# MesureAlimentation.net
KiCad netlist of a schematic drawn in Altium Designer
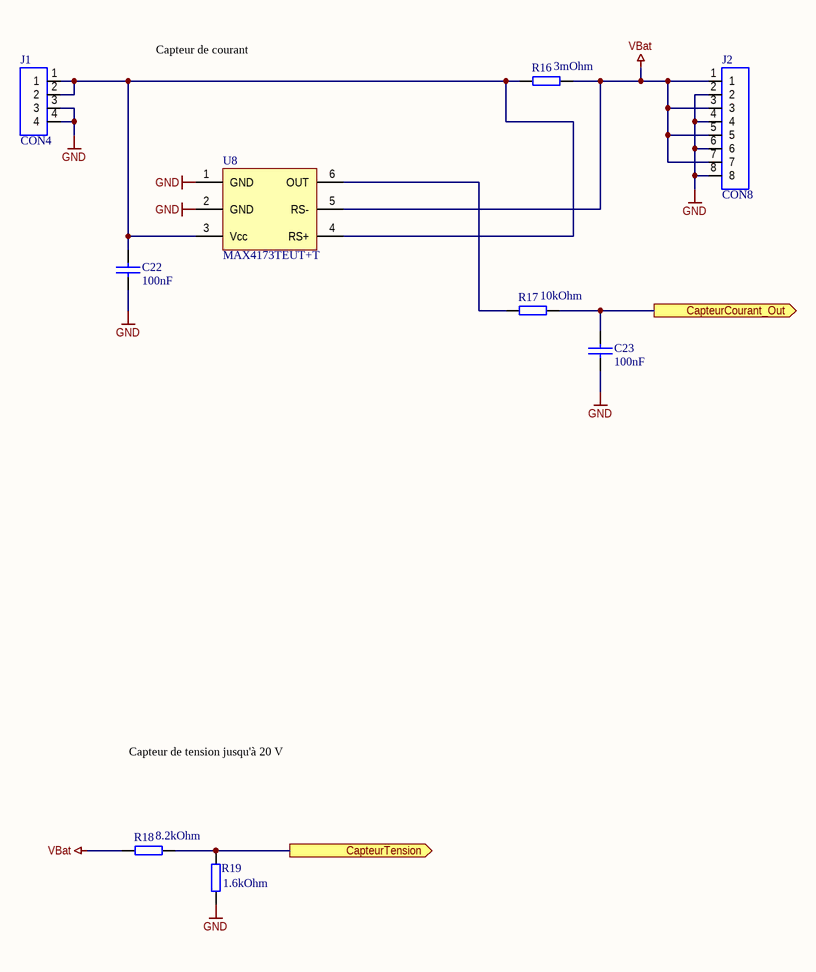
[diagram p0: MesureAlimentation.SchDoc]

(export (version "E")
  (design (tool "Eeschema 10.0.6"))
  (components
    (comp (ref "C22")
      (value "100nF")
      (footprint "060301")
      (description "CAPA")
      (fields (field (name "Comment") "GRM188R71E104KA01D"))
      (libsource (lib "General-Sch-205") (part "CAPA"))
    )
    (comp (ref "C23")
      (value "100nF")
      (footprint "060301")
      (description "CAPA")
      (fields (field (name "Comment") "GRM188R71E104KA01D"))
      (libsource (lib "General-Sch-205") (part "CAPA"))
    )
    (comp (ref "J1") (value "CON4") (footprint "SL354D") (libsource (lib "EISI") (part "CON4")))
    (comp (ref "J2") (value "CON8") (footprint "SL358D") (libsource (lib "EISI") (part "CON8")))
    (comp (ref "R16")
      (value "3mOhm")
      (footprint "5.2x8.75")
      (fields (field (name "Comment") "WSLP59313L000FEB"))
      (libsource (lib "General-Sch-205") (part "RES"))
    )
    (comp (ref "R17")
      (value "10kOhm")
      (footprint "080501")
      (fields (field (name "Comment") "ERJ-6GEYJ103V"))
      (libsource (lib "General-Sch-205") (part "RES"))
    )
    (comp (ref "R18")
      (value "8.2kOhm")
      (footprint "080501")
      (fields (field (name "Comment") "ERJ-6GEYJ822V"))
      (libsource (lib "General-Sch-205") (part "RES"))
    )
    (comp (ref "R19")
      (value "1.6kOhm")
      (footprint "080501")
      (fields (field (name "Comment") "ERJ-6GEYJ162V"))
      (libsource (lib "General-Sch-205") (part "RES"))
    )
    (comp (ref "U8")
      (value "MAX4173TEUT+T")
      (footprint "SOT26A-6AM")
      (description "Amplificateur capteur de courant")
      (libsource (lib "Schlib1") (part "Max4173"))
    )
  )
  (nets
    (net (code "1") (name "/CapteurCourant_Out") (class "Default")
      (node (ref "C23") (pin "1") (pintype "passive"))
      (node (ref "R17") (pin "2") (pintype "passive"))
    )
    (net (code "2") (name "/CapteurTension") (class "Default")
      (node (ref "R18") (pin "2") (pintype "passive"))
      (node (ref "R19") (pin "1") (pintype "passive"))
    )
    (net (code "3") (name "GND") (class "Default")
      (node (ref "C22") (pin "2") (pintype "passive"))
      (node (ref "C23") (pin "2") (pintype "passive"))
      (node (ref "J1") (pin "3") (pinfunction "3_3") (pintype "passive"))
      (node (ref "J1") (pin "4") (pinfunction "4_4") (pintype "passive"))
      (node (ref "J2") (pin "2") (pinfunction "2_2") (pintype "passive"))
      (node (ref "J2") (pin "4") (pinfunction "4_4") (pintype "passive"))
      (node (ref "J2") (pin "6") (pinfunction "6_6") (pintype "passive"))
      (node (ref "J2") (pin "8") (pinfunction "8_8") (pintype "passive"))
      (node (ref "R19") (pin "2") (pintype "passive"))
      (node (ref "U8") (pin "1") (pinfunction "GND_1") (pintype "passive"))
      (node (ref "U8") (pin "2") (pinfunction "GND_2") (pintype "passive"))
    )
    (net (code "4") (name "Net-(U8-OUT)") (class "Default")
      (node (ref "R17") (pin "1") (pintype "passive"))
      (node (ref "U8") (pin "6") (pinfunction "OUT_6") (pintype "passive"))
    )
    (net (code "5") (name "Net-(U8-RS+)") (class "Default")
      (node (ref "C22") (pin "1") (pintype "passive"))
      (node (ref "J1") (pin "1") (pinfunction "1_1") (pintype "passive"))
      (node (ref "J1") (pin "2") (pinfunction "2_2") (pintype "passive"))
      (node (ref "R16") (pin "1") (pintype "passive"))
      (node (ref "U8") (pin "3") (pinfunction "Vcc_3") (pintype "passive"))
      (node (ref "U8") (pin "4") (pinfunction "RS+_4") (pintype "passive"))
    )
    (net (code "6") (name "VBat") (class "Default")
      (node (ref "J2") (pin "1") (pinfunction "1_1") (pintype "passive"))
      (node (ref "J2") (pin "3") (pinfunction "3_3") (pintype "passive"))
      (node (ref "J2") (pin "5") (pinfunction "5_5") (pintype "passive"))
      (node (ref "J2") (pin "7") (pinfunction "7_7") (pintype "passive"))
      (node (ref "R16") (pin "2") (pintype "passive"))
      (node (ref "R18") (pin "1") (pintype "passive"))
      (node (ref "U8") (pin "5") (pinfunction "RS-_5") (pintype "passive"))
    )
  )
)
